# ATtiny85_Handheld.net
KiCad netlist of a schematic drawn in EAGLE
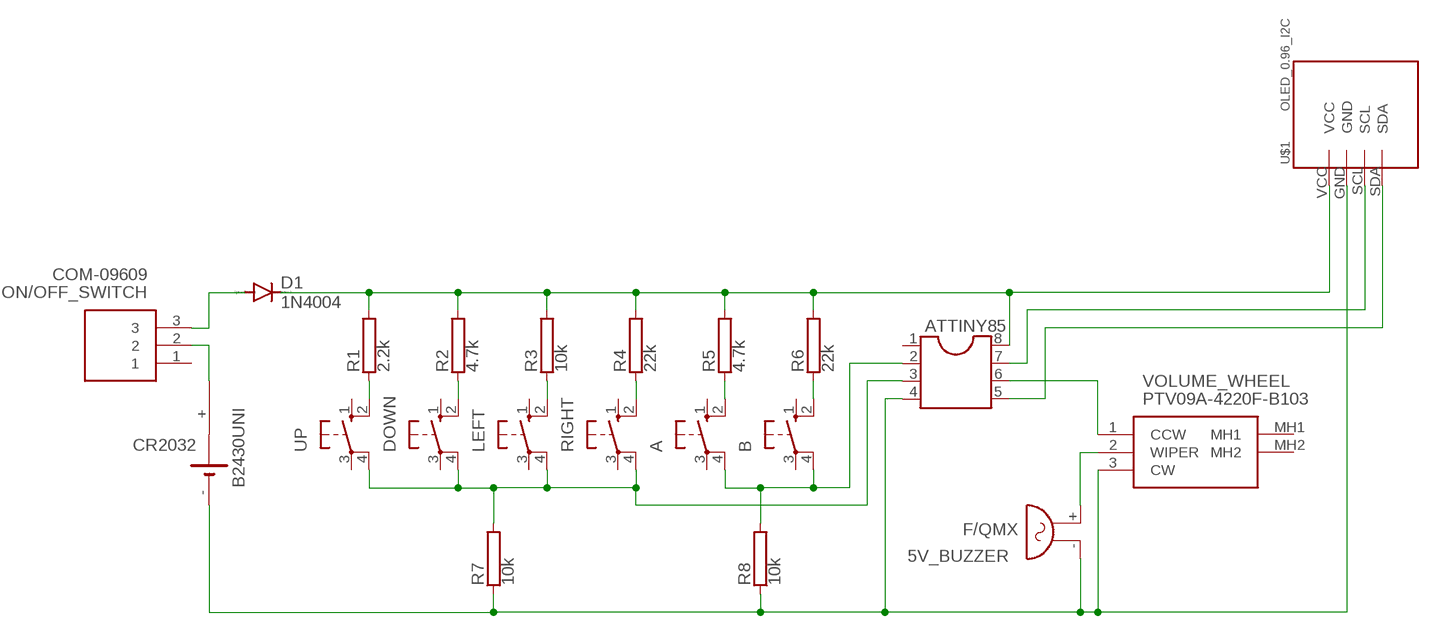
[diagram p0: schematic, sheet 1]

(export (version "E")
  (design (tool "Eeschema 10.0.6"))
  (components
    (comp (ref "5V_BUZZER")
      (value "F/QMX")
      (footprint "eagle-import:F_QMX")
      (libsource (lib "eagle-import") (part "F/QMX"))
    )
    (comp (ref "A")
      (value "10-XX")
      (footprint "eagle-import:B3F-10XX")
      (fields (field (name "MPN") "B3F-1000"))
      (libsource (lib "eagle-import") (part "10-XX"))
    )
    (comp (ref "ATTINY85")
      (value "DIL8")
      (footprint "eagle-import:DIL08")
      (libsource (lib "eagle-import") (part "DIL8"))
    )
    (comp (ref "B")
      (value "10-XX")
      (footprint "eagle-import:B3F-10XX")
      (fields (field (name "MPN") "B3F-1000"))
      (libsource (lib "eagle-import") (part "10-XX"))
    )
    (comp (ref "CR2032")
      (value "B2430UNI")
      (footprint "eagle-import:B2430UNI")
      (libsource (lib "eagle-import") (part "B2430UNI"))
    )
    (comp (ref "D1")
      (value "1N4004")
      (footprint "eagle-import:DO41-10")
      (libsource (lib "eagle-import") (part "1N4004"))
    )
    (comp (ref "DOWN")
      (value "10-XX")
      (footprint "eagle-import:B3F-10XX")
      (fields (field (name "MPN") "B3F-1000"))
      (libsource (lib "eagle-import") (part "10-XX"))
    )
    (comp (ref "LEFT")
      (value "10-XX")
      (footprint "eagle-import:B3F-10XX")
      (fields (field (name "MPN") "B3F-1000"))
      (libsource (lib "eagle-import") (part "10-XX"))
    )
    (comp (ref "ON/OFF_SWITCH")
      (value "COM-09609")
      (footprint "eagle-import:COM09609")
      (fields (field (name "MOUSER_PART_NUMBER") "474-COM-09609"))
      (libsource (lib "eagle-import") (part "COM-09609"))
    )
    (comp (ref "R1")
      (value "2.2k")
      (footprint "eagle-import:AC01")
      (libsource (lib "eagle-import") (part "RAC01"))
    )
    (comp (ref "R2")
      (value "4.7k")
      (footprint "eagle-import:AC01")
      (libsource (lib "eagle-import") (part "RAC01"))
    )
    (comp (ref "R3")
      (value "10k")
      (footprint "eagle-import:AC01")
      (libsource (lib "eagle-import") (part "RAC01"))
    )
    (comp (ref "R4")
      (value "22k")
      (footprint "eagle-import:AC01")
      (libsource (lib "eagle-import") (part "RAC01"))
    )
    (comp (ref "R5")
      (value "4.7k")
      (footprint "eagle-import:AC01")
      (libsource (lib "eagle-import") (part "RAC01"))
    )
    (comp (ref "R6")
      (value "22k")
      (footprint "eagle-import:AC01")
      (libsource (lib "eagle-import") (part "RAC01"))
    )
    (comp (ref "R7")
      (value "10k")
      (footprint "eagle-import:AC01")
      (libsource (lib "eagle-import") (part "RAC01"))
    )
    (comp (ref "R8")
      (value "10k")
      (footprint "eagle-import:AC01")
      (libsource (lib "eagle-import") (part "RAC01"))
    )
    (comp (ref "RIGHT")
      (value "10-XX")
      (footprint "eagle-import:B3F-10XX")
      (fields (field (name "MPN") "B3F-1000"))
      (libsource (lib "eagle-import") (part "10-XX"))
    )
    (comp (ref "U$1")
      (value "OLED_0.96_I2C")
      (footprint "eagle-import:OLED_0.96_I2C")
      (libsource (lib "eagle-import") (part "OLED_0.96_I2C"))
    )
    (comp (ref "UP")
      (value "10-XX")
      (footprint "eagle-import:B3F-10XX")
      (fields (field (name "MPN") "B3F-1000"))
      (libsource (lib "eagle-import") (part "10-XX"))
    )
    (comp (ref "VOLUME_WHEEL")
      (value "PTV09A-4220F-B103")
      (footprint "eagle-import:PTV09A4220FB103")
      (fields (field (name "MOUSER_PART_NUMBER") "652-PTV09A-4220FB103"))
      (libsource (lib "eagle-import") (part "PTV09A-4220F-B103"))
    )
  )
  (nets
    (net (code "1") (name "Net-(5V_BUZZER-1)") (class "Default")
      (node (ref "5V_BUZZER") (pin "-") (pinfunction "1_-") (pintype "passive"))
      (node (ref "ATTINY85") (pin "4") (pinfunction "4_4") (pintype "passive"))
      (node (ref "CR2032") (pin "-") (pinfunction "-_-") (pintype "passive"))
      (node (ref "R7") (pin "1") (pinfunction "1_1") (pintype "passive"))
      (node (ref "R8") (pin "1") (pinfunction "1_1") (pintype "passive"))
      (node (ref "U$1") (pin "GND") (pinfunction "GND_GND") (pintype "bidirectional"))
      (node (ref "VOLUME_WHEEL") (pin "3") (pinfunction "CW_3") (pintype "bidirectional"))
    )
    (net (code "2") (name "Net-(5V_BUZZER-2)") (class "Default")
      (node (ref "5V_BUZZER") (pin "+") (pinfunction "2_+") (pintype "passive"))
      (node (ref "VOLUME_WHEEL") (pin "2") (pinfunction "WIPER_2") (pintype "bidirectional"))
    )
    (net (code "3") (name "Net-(A-P1)") (class "Default")
      (node (ref "A") (pin "4") (pinfunction "P1_4") (pintype "passive"))
      (node (ref "ATTINY85") (pin "2") (pinfunction "2_2") (pintype "passive"))
      (node (ref "B") (pin "4") (pinfunction "P1_4") (pintype "passive"))
      (node (ref "R8") (pin "2") (pinfunction "2_2") (pintype "passive"))
    )
    (net (code "4") (name "Net-(A-S1)") (class "Default")
      (node (ref "A") (pin "2") (pinfunction "S1_2") (pintype "passive"))
      (node (ref "R5") (pin "1") (pinfunction "1_1") (pintype "passive"))
    )
    (net (code "5") (name "Net-(ATTINY85-Pad5)") (class "Default")
      (node (ref "ATTINY85") (pin "5") (pinfunction "5_5") (pintype "passive"))
      (node (ref "U$1") (pin "SDA") (pinfunction "SDA_SDA") (pintype "bidirectional"))
    )
    (net (code "6") (name "Net-(ATTINY85-Pad7)") (class "Default")
      (node (ref "ATTINY85") (pin "7") (pinfunction "7_7") (pintype "passive"))
      (node (ref "U$1") (pin "SCL") (pinfunction "SCL_SCL") (pintype "bidirectional"))
    )
    (net (code "7") (name "Net-(ATTINY85-Pad8)") (class "Default")
      (node (ref "ATTINY85") (pin "8") (pinfunction "8_8") (pintype "passive"))
      (node (ref "D1") (pin "C") (pinfunction "C_C") (pintype "passive"))
      (node (ref "R1") (pin "2") (pinfunction "2_2") (pintype "passive"))
      (node (ref "R2") (pin "2") (pinfunction "2_2") (pintype "passive"))
      (node (ref "R3") (pin "2") (pinfunction "2_2") (pintype "passive"))
      (node (ref "R4") (pin "2") (pinfunction "2_2") (pintype "passive"))
      (node (ref "R5") (pin "2") (pinfunction "2_2") (pintype "passive"))
      (node (ref "R6") (pin "2") (pinfunction "2_2") (pintype "passive"))
      (node (ref "U$1") (pin "VCC") (pinfunction "VCC_VCC") (pintype "bidirectional"))
    )
    (net (code "8") (name "Net-(B-S1)") (class "Default")
      (node (ref "B") (pin "2") (pinfunction "S1_2") (pintype "passive"))
      (node (ref "R6") (pin "1") (pinfunction "1_1") (pintype "passive"))
    )
    (net (code "9") (name "Net-(CR2032-Pad+)") (class "Default")
      (node (ref "CR2032") (pin "+") (pinfunction "+_+") (pintype "passive"))
      (node (ref "ON/OFF_SWITCH") (pin "2") (pinfunction "2_2") (pintype "bidirectional"))
    )
    (net (code "10") (name "Net-(D1-PadA)") (class "Default")
      (node (ref "D1") (pin "A") (pinfunction "A_A") (pintype "passive"))
      (node (ref "ON/OFF_SWITCH") (pin "3") (pinfunction "3_3") (pintype "bidirectional"))
    )
    (net (code "11") (name "Net-(DOWN-P1)") (class "Default")
      (node (ref "ATTINY85") (pin "3") (pinfunction "3_3") (pintype "passive"))
      (node (ref "DOWN") (pin "4") (pinfunction "P1_4") (pintype "passive"))
      (node (ref "LEFT") (pin "4") (pinfunction "P1_4") (pintype "passive"))
      (node (ref "R7") (pin "2") (pinfunction "2_2") (pintype "passive"))
      (node (ref "RIGHT") (pin "4") (pinfunction "P1_4") (pintype "passive"))
      (node (ref "UP") (pin "4") (pinfunction "P1_4") (pintype "passive"))
    )
    (net (code "12") (name "Net-(DOWN-S1)") (class "Default")
      (node (ref "DOWN") (pin "2") (pinfunction "S1_2") (pintype "passive"))
      (node (ref "R2") (pin "1") (pinfunction "1_1") (pintype "passive"))
    )
    (net (code "13") (name "Net-(LEFT-S1)") (class "Default")
      (node (ref "LEFT") (pin "2") (pinfunction "S1_2") (pintype "passive"))
      (node (ref "R3") (pin "1") (pinfunction "1_1") (pintype "passive"))
    )
    (net (code "14") (name "Net-(RIGHT-S1)") (class "Default")
      (node (ref "R4") (pin "1") (pinfunction "1_1") (pintype "passive"))
      (node (ref "RIGHT") (pin "2") (pinfunction "S1_2") (pintype "passive"))
    )
    (net (code "15") (name "Net-(UP-S1)") (class "Default")
      (node (ref "R1") (pin "1") (pinfunction "1_1") (pintype "passive"))
      (node (ref "UP") (pin "2") (pinfunction "S1_2") (pintype "passive"))
    )
    (net (code "16") (name "Net-(VOLUME_WHEEL-CCW)") (class "Default")
      (node (ref "ATTINY85") (pin "6") (pinfunction "6_6") (pintype "passive"))
      (node (ref "VOLUME_WHEEL") (pin "1") (pinfunction "CCW_1") (pintype "bidirectional"))
    )
    (net (code "17") (name "unconnected-(A-P-Pad3)") (class "Default")
      (node (ref "A") (pin "3") (pinfunction "P_3") (pintype "passive"))
    )
    (net (code "18") (name "unconnected-(A-S-Pad1)") (class "Default")
      (node (ref "A") (pin "1") (pinfunction "S_1") (pintype "passive"))
    )
    (net (code "19") (name "unconnected-(ATTINY85-Pad1)") (class "Default")
      (node (ref "ATTINY85") (pin "1") (pinfunction "1_1") (pintype "passive"))
    )
    (net (code "20") (name "unconnected-(B-P-Pad3)") (class "Default")
      (node (ref "B") (pin "3") (pinfunction "P_3") (pintype "passive"))
    )
    (net (code "21") (name "unconnected-(B-S-Pad1)") (class "Default")
      (node (ref "B") (pin "1") (pinfunction "S_1") (pintype "passive"))
    )
    (net (code "22") (name "unconnected-(CR2032-+-Pad+@1)") (class "Default")
      (node (ref "CR2032") (pin "+@1") (pinfunction "+_+@1") (pintype "passive"))
    )
    (net (code "23") (name "unconnected-(CR2032-+-Pad+@2)") (class "Default")
      (node (ref "CR2032") (pin "+@2") (pinfunction "+_+@2") (pintype "passive"))
    )
    (net (code "24") (name "unconnected-(CR2032-+-Pad+@3)") (class "Default")
      (node (ref "CR2032") (pin "+@3") (pinfunction "+_+@3") (pintype "passive"))
    )
    (net (code "25") (name "unconnected-(CR2032-+-Pad+@4)") (class "Default")
      (node (ref "CR2032") (pin "+@4") (pinfunction "+_+@4") (pintype "passive"))
    )
    (net (code "26") (name "unconnected-(CR2032---Pad-@1)") (class "Default")
      (node (ref "CR2032") (pin "-@1") (pinfunction "-_-@1") (pintype "passive"))
    )
    (net (code "27") (name "unconnected-(DOWN-P-Pad3)") (class "Default")
      (node (ref "DOWN") (pin "3") (pinfunction "P_3") (pintype "passive"))
    )
    (net (code "28") (name "unconnected-(DOWN-S-Pad1)") (class "Default")
      (node (ref "DOWN") (pin "1") (pinfunction "S_1") (pintype "passive"))
    )
    (net (code "29") (name "unconnected-(LEFT-P-Pad3)") (class "Default")
      (node (ref "LEFT") (pin "3") (pinfunction "P_3") (pintype "passive"))
    )
    (net (code "30") (name "unconnected-(LEFT-S-Pad1)") (class "Default")
      (node (ref "LEFT") (pin "1") (pinfunction "S_1") (pintype "passive"))
    )
    (net (code "31") (name "unconnected-(ON/OFF_SWITCH-Pad1)") (class "Default")
      (node (ref "ON/OFF_SWITCH") (pin "1") (pinfunction "1_1") (pintype "bidirectional"))
    )
    (net (code "32") (name "unconnected-(RIGHT-P-Pad3)") (class "Default")
      (node (ref "RIGHT") (pin "3") (pinfunction "P_3") (pintype "passive"))
    )
    (net (code "33") (name "unconnected-(RIGHT-S-Pad1)") (class "Default")
      (node (ref "RIGHT") (pin "1") (pinfunction "S_1") (pintype "passive"))
    )
    (net (code "34") (name "unconnected-(UP-P-Pad3)") (class "Default")
      (node (ref "UP") (pin "3") (pinfunction "P_3") (pintype "passive"))
    )
    (net (code "35") (name "unconnected-(UP-S-Pad1)") (class "Default")
      (node (ref "UP") (pin "1") (pinfunction "S_1") (pintype "passive"))
    )
    (net (code "36") (name "unconnected-(VOLUME_WHEEL-PadMH1)") (class "Default")
      (node (ref "VOLUME_WHEEL") (pin "MH1") (pinfunction "MH1_MH1") (pintype "bidirectional"))
    )
    (net (code "37") (name "unconnected-(VOLUME_WHEEL-PadMH2)") (class "Default")
      (node (ref "VOLUME_WHEEL") (pin "MH2") (pinfunction "MH2_MH2") (pintype "bidirectional"))
    )
  )
)
